# feedback-strobe.net
KiCad netlist of a schematic drawn in EAGLE
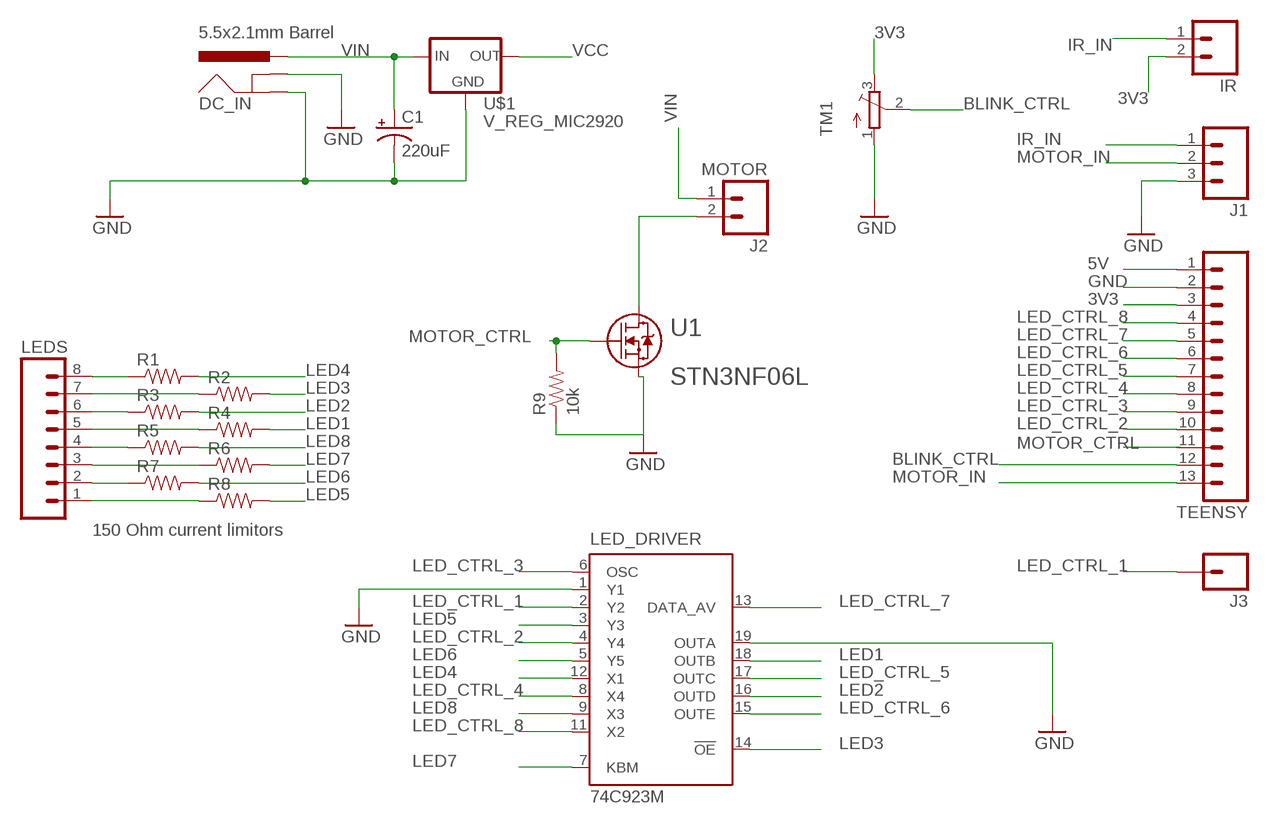
[diagram p0: schematic, sheet 1]

(export (version "E")
  (design (tool "Eeschema 10.0.6"))
  (components
    (comp (ref "C1")
      (value "220uF")
      (footprint "eagle-import:NIPPON_F80")
      (libsource (lib "eagle-import") (part "CAP_POLF80"))
    )
    (comp (ref "DC_IN")
      (value "5.5x2.1mm Barrel")
      (footprint "eagle-import:POWER_JACK_SMD")
      (libsource (lib "eagle-import") (part "POWER_JACKSMD"))
    )
    (comp (ref "IR")
      (value "M02PTH")
      (footprint "eagle-import:1X02")
      (libsource (lib "eagle-import") (part "M02PTH"))
    )
    (comp (ref "J1")
      (value "M03PTH")
      (footprint "eagle-import:1X03")
      (libsource (lib "eagle-import") (part "M03PTH"))
    )
    (comp (ref "J2")
      (value "MOTOR")
      (footprint "eagle-import:1X02")
      (libsource (lib "eagle-import") (part "M02PTH"))
    )
    (comp (ref "J3")
      (value "M01PTH")
      (footprint "eagle-import:1X01")
      (libsource (lib "eagle-import") (part "M01PTH"))
    )
    (comp (ref "LEDS")
      (value "M08")
      (footprint "eagle-import:1X08_ROUND")
      (libsource (lib "eagle-import") (part "M08"))
    )
    (comp (ref "LED_DRIVER")
      (value "74C923M")
      (footprint "eagle-import:SO20W")
      (libsource (lib "eagle-import") (part "74C923M"))
    )
    (comp (ref "R1")
      (value "RESISTOR0603-RES")
      (footprint "eagle-import:0603-RES")
      (libsource (lib "eagle-import") (part "RESISTOR0603-RES"))
    )
    (comp (ref "R2")
      (value "RESISTOR0603-RES")
      (footprint "eagle-import:0603-RES")
      (libsource (lib "eagle-import") (part "RESISTOR0603-RES"))
    )
    (comp (ref "R3")
      (value "RESISTOR0603-RES")
      (footprint "eagle-import:0603-RES")
      (libsource (lib "eagle-import") (part "RESISTOR0603-RES"))
    )
    (comp (ref "R4")
      (value "RESISTOR0603-RES")
      (footprint "eagle-import:0603-RES")
      (libsource (lib "eagle-import") (part "RESISTOR0603-RES"))
    )
    (comp (ref "R5")
      (value "RESISTOR0603-RES")
      (footprint "eagle-import:0603-RES")
      (libsource (lib "eagle-import") (part "RESISTOR0603-RES"))
    )
    (comp (ref "R6")
      (value "RESISTOR0603-RES")
      (footprint "eagle-import:0603-RES")
      (libsource (lib "eagle-import") (part "RESISTOR0603-RES"))
    )
    (comp (ref "R7")
      (value "RESISTOR0603-RES")
      (footprint "eagle-import:0603-RES")
      (libsource (lib "eagle-import") (part "RESISTOR0603-RES"))
    )
    (comp (ref "R8")
      (value "RESISTOR0603-RES")
      (footprint "eagle-import:0603-RES")
      (libsource (lib "eagle-import") (part "RESISTOR0603-RES"))
    )
    (comp (ref "R9")
      (value "10k")
      (footprint "eagle-import:0603-RES")
      (libsource (lib "eagle-import") (part "RESISTOR0603-RES"))
    )
    (comp (ref "TEENSY")
      (value "M13")
      (footprint "eagle-import:1X13")
      (libsource (lib "eagle-import") (part "M13"))
    )
    (comp (ref "TM1")
      (value "TRIMPOT3386")
      (footprint "eagle-import:TRIM-3386")
      (libsource (lib "eagle-import") (part "TRIMPOT3386"))
    )
    (comp (ref "U$1")
      (value "V_REG_MIC2920")
      (footprint "eagle-import:SOT223")
      (libsource (lib "eagle-import") (part "V_REG_MIC2920"))
    )
    (comp (ref "U1")
      (value "STN3NF06L")
      (footprint "eagle-import:SOT-223")
      (fields
        (field (name "DIGIKEYPARTNUMBER") "49731772ND")
        (field (name "COPYRIGHT") "Copyright C 2015 Accelerated Designs. All rights reserved")
      )
      (libsource (lib "eagle-import") (part "STN3NF06L"))
    )
  )
  (nets
    (net (code "1") (name "/3V3") (class "Default")
      (node (ref "IR") (pin "2") (pinfunction "2_2") (pintype "passive"))
      (node (ref "TEENSY") (pin "3") (pinfunction "3_3") (pintype "passive"))
      (node (ref "TM1") (pin "3") (pinfunction "E_3") (pintype "passive"))
    )
    (net (code "2") (name "/5V") (class "Default")
      (node (ref "TEENSY") (pin "1") (pinfunction "1_1") (pintype "passive"))
    )
    (net (code "3") (name "/BLINK_CTRL") (class "Default")
      (node (ref "TEENSY") (pin "12") (pinfunction "12_12") (pintype "passive"))
      (node (ref "TM1") (pin "2") (pinfunction "S_2") (pintype "passive"))
    )
    (net (code "4") (name "/IR_IN") (class "Default")
      (node (ref "IR") (pin "1") (pinfunction "1_1") (pintype "passive"))
      (node (ref "J1") (pin "1") (pinfunction "1_1") (pintype "passive"))
    )
    (net (code "5") (name "/LED1") (class "Default")
      (node (ref "LED_DRIVER") (pin "18") (pinfunction "OUTB_18") (pintype "output"))
      (node (ref "R4") (pin "2") (pinfunction "2_2") (pintype "passive"))
    )
    (net (code "6") (name "/LED2") (class "Default")
      (node (ref "LED_DRIVER") (pin "16") (pinfunction "OUTD_16") (pintype "output"))
      (node (ref "R3") (pin "2") (pinfunction "2_2") (pintype "passive"))
    )
    (net (code "7") (name "/LED3") (class "Default")
      (node (ref "LED_DRIVER") (pin "14") (pinfunction "~{OE}_14") (pintype "input"))
      (node (ref "R2") (pin "2") (pinfunction "2_2") (pintype "passive"))
    )
    (net (code "8") (name "/LED4") (class "Default")
      (node (ref "LED_DRIVER") (pin "12") (pinfunction "X1_12") (pintype "input"))
      (node (ref "R1") (pin "2") (pinfunction "2_2") (pintype "passive"))
    )
    (net (code "9") (name "/LED5") (class "Default")
      (node (ref "LED_DRIVER") (pin "3") (pinfunction "Y3_3") (pintype "input"))
      (node (ref "R8") (pin "2") (pinfunction "2_2") (pintype "passive"))
    )
    (net (code "10") (name "/LED6") (class "Default")
      (node (ref "LED_DRIVER") (pin "5") (pinfunction "Y5_5") (pintype "input"))
      (node (ref "R7") (pin "2") (pinfunction "2_2") (pintype "passive"))
    )
    (net (code "11") (name "/LED7") (class "Default")
      (node (ref "LED_DRIVER") (pin "7") (pinfunction "KBM_7") (pintype "input"))
      (node (ref "R6") (pin "2") (pinfunction "2_2") (pintype "passive"))
    )
    (net (code "12") (name "/LED8") (class "Default")
      (node (ref "LED_DRIVER") (pin "9") (pinfunction "X3_9") (pintype "input"))
      (node (ref "R5") (pin "2") (pinfunction "2_2") (pintype "passive"))
    )
    (net (code "13") (name "/LED_CTRL_1") (class "Default")
      (node (ref "J3") (pin "1") (pinfunction "1_1") (pintype "passive"))
      (node (ref "LED_DRIVER") (pin "2") (pinfunction "Y2_2") (pintype "input"))
    )
    (net (code "14") (name "/LED_CTRL_2") (class "Default")
      (node (ref "LED_DRIVER") (pin "4") (pinfunction "Y4_4") (pintype "input"))
      (node (ref "TEENSY") (pin "10") (pinfunction "10_10") (pintype "passive"))
    )
    (net (code "15") (name "/LED_CTRL_3") (class "Default")
      (node (ref "LED_DRIVER") (pin "6") (pinfunction "OSC_6") (pintype "input"))
      (node (ref "TEENSY") (pin "9") (pinfunction "9_9") (pintype "passive"))
    )
    (net (code "16") (name "/LED_CTRL_4") (class "Default")
      (node (ref "LED_DRIVER") (pin "8") (pinfunction "X4_8") (pintype "input"))
      (node (ref "TEENSY") (pin "8") (pinfunction "8_8") (pintype "passive"))
    )
    (net (code "17") (name "/LED_CTRL_5") (class "Default")
      (node (ref "LED_DRIVER") (pin "17") (pinfunction "OUTC_17") (pintype "output"))
      (node (ref "TEENSY") (pin "7") (pinfunction "7_7") (pintype "passive"))
    )
    (net (code "18") (name "/LED_CTRL_6") (class "Default")
      (node (ref "LED_DRIVER") (pin "15") (pinfunction "OUTE_15") (pintype "output"))
      (node (ref "TEENSY") (pin "6") (pinfunction "6_6") (pintype "passive"))
    )
    (net (code "19") (name "/LED_CTRL_7") (class "Default")
      (node (ref "LED_DRIVER") (pin "13") (pinfunction "DATA_AV_13") (pintype "output"))
      (node (ref "TEENSY") (pin "5") (pinfunction "5_5") (pintype "passive"))
    )
    (net (code "20") (name "/LED_CTRL_8") (class "Default")
      (node (ref "LED_DRIVER") (pin "11") (pinfunction "X2_11") (pintype "input"))
      (node (ref "TEENSY") (pin "4") (pinfunction "4_4") (pintype "passive"))
    )
    (net (code "21") (name "/MOTOR_CTRL") (class "Default")
      (node (ref "R9") (pin "2") (pinfunction "2_2") (pintype "passive"))
      (node (ref "U1") (pin "1") (pinfunction "1_1") (pintype "passive"))
    )
    (net (code "22") (name "/MOTOR_IN") (class "Default")
      (node (ref "J1") (pin "2") (pinfunction "2_2") (pintype "passive"))
      (node (ref "TEENSY") (pin "13") (pinfunction "13_13") (pintype "passive"))
    )
    (net (code "23") (name "/VCC") (class "Default")
      (node (ref "U$1") (pin "3") (pinfunction "OUT_3") (pintype "passive"))
    )
    (net (code "24") (name "/VIN") (class "Default")
      (node (ref "C1") (pin "+") (pinfunction "+_+") (pintype "passive"))
      (node (ref "DC_IN") (pin "VIN0") (pinfunction "PWR_VIN0") (pintype "bidirectional"))
      (node (ref "J2") (pin "1") (pinfunction "1_1") (pintype "passive"))
      (node (ref "U$1") (pin "1") (pinfunction "IN_1") (pintype "input"))
    )
    (net (code "25") (name "GND") (class "Default")
      (node (ref "C1") (pin "-") (pinfunction "-_-") (pintype "passive"))
      (node (ref "DC_IN") (pin "GND") (pinfunction "GNDBREAK_GND") (pintype "bidirectional"))
      (node (ref "DC_IN") (pin "P$4") (pinfunction "GND_P$4") (pintype "bidirectional"))
      (node (ref "J1") (pin "3") (pinfunction "3_3") (pintype "passive"))
      (node (ref "LED_DRIVER") (pin "1") (pinfunction "Y1_1") (pintype "input"))
      (node (ref "LED_DRIVER") (pin "19") (pinfunction "OUTA_19") (pintype "output"))
      (node (ref "R9") (pin "1") (pinfunction "1_1") (pintype "passive"))
      (node (ref "TEENSY") (pin "2") (pinfunction "2_2") (pintype "passive"))
      (node (ref "TM1") (pin "1") (pinfunction "A_1") (pintype "passive"))
      (node (ref "U$1") (pin "2") (pinfunction "GND_2") (pintype "input"))
      (node (ref "U1") (pin "3") (pinfunction "3_3") (pintype "passive"))
    )
    (net (code "26") (name "Net-(J2-Pad2)") (class "Default")
      (node (ref "J2") (pin "2") (pinfunction "2_2") (pintype "passive"))
      (node (ref "U1") (pin "2") (pinfunction "2_2") (pintype "passive"))
    )
    (net (code "27") (name "Net-(LEDS-Pad1)") (class "Default")
      (node (ref "LEDS") (pin "1") (pinfunction "1_1") (pintype "passive"))
      (node (ref "R8") (pin "1") (pinfunction "1_1") (pintype "passive"))
    )
    (net (code "28") (name "Net-(LEDS-Pad2)") (class "Default")
      (node (ref "LEDS") (pin "2") (pinfunction "2_2") (pintype "passive"))
      (node (ref "R7") (pin "1") (pinfunction "1_1") (pintype "passive"))
    )
    (net (code "29") (name "Net-(LEDS-Pad3)") (class "Default")
      (node (ref "LEDS") (pin "3") (pinfunction "3_3") (pintype "passive"))
      (node (ref "R6") (pin "1") (pinfunction "1_1") (pintype "passive"))
    )
    (net (code "30") (name "Net-(LEDS-Pad4)") (class "Default")
      (node (ref "LEDS") (pin "4") (pinfunction "4_4") (pintype "passive"))
      (node (ref "R5") (pin "1") (pinfunction "1_1") (pintype "passive"))
    )
    (net (code "31") (name "Net-(LEDS-Pad5)") (class "Default")
      (node (ref "LEDS") (pin "5") (pinfunction "5_5") (pintype "passive"))
      (node (ref "R4") (pin "1") (pinfunction "1_1") (pintype "passive"))
    )
    (net (code "32") (name "Net-(LEDS-Pad6)") (class "Default")
      (node (ref "LEDS") (pin "6") (pinfunction "6_6") (pintype "passive"))
      (node (ref "R3") (pin "1") (pinfunction "1_1") (pintype "passive"))
    )
    (net (code "33") (name "Net-(LEDS-Pad7)") (class "Default")
      (node (ref "LEDS") (pin "7") (pinfunction "7_7") (pintype "passive"))
      (node (ref "R2") (pin "1") (pinfunction "1_1") (pintype "passive"))
    )
    (net (code "34") (name "Net-(LEDS-Pad8)") (class "Default")
      (node (ref "LEDS") (pin "8") (pinfunction "8_8") (pintype "passive"))
      (node (ref "R1") (pin "1") (pinfunction "1_1") (pintype "passive"))
    )
    (net (code "35") (name "unconnected-(TEENSY-Pad11)") (class "Default")
      (node (ref "TEENSY") (pin "11") (pinfunction "11_11") (pintype "passive"))
    )
  )
)
